# StreamDeck_CPU2-V0.net
KiCad netlist of a schematic drawn in Altium Designer
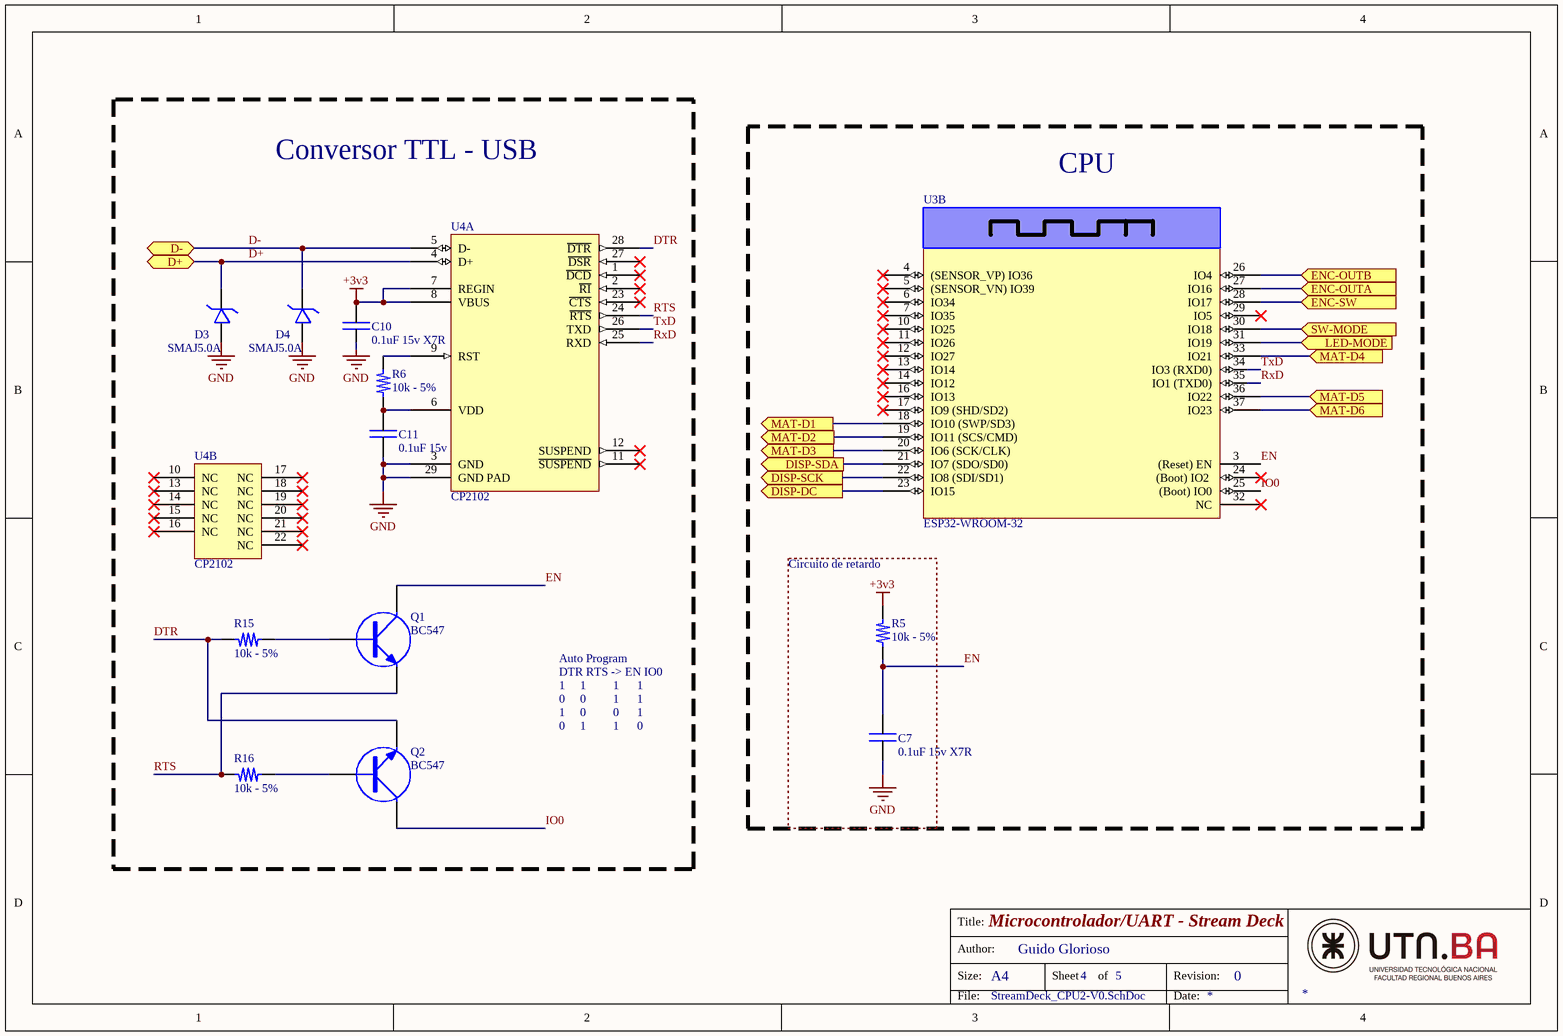
[diagram p0: StreamDeck_CPU2-V0.SchDoc]

(export (version "E")
  (design (tool "Eeschema 10.0.6"))
  (components
    (comp (ref "C7")
      (value "0.1uF 15v X7R")
      (footprint "C_0805")
      (description "Capacitor no polarizado")
      (libsource (lib "StreamDeck-V0") (part "Capacitor NP"))
    )
    (comp (ref "C10")
      (value "0.1uF 15v X7R")
      (footprint "C_0805")
      (description "Capacitor no polarizado")
      (libsource (lib "StreamDeck-V0") (part "Capacitor NP"))
    )
    (comp (ref "C11")
      (value "0.1uF 15v X7R")
      (footprint "C_0805")
      (description "Capacitor no polarizado")
      (libsource (lib "StreamDeck-V0") (part "Capacitor NP"))
    )
    (comp (ref "D3")
      (value "SMAJ5.0A")
      (footprint "D_SMA")
      (description "Diodo TVS")
      (libsource (lib "StreamDeck-V0") (part "Diodo TVS"))
    )
    (comp (ref "D4")
      (value "SMAJ5.0A")
      (footprint "D_SMA")
      (description "Diodo TVS")
      (libsource (lib "StreamDeck-V0") (part "Diodo TVS"))
    )
    (comp (ref "Q1")
      (value "BC547")
      (footprint "SOT_23")
      (description "Transistor bipolar NPN - Encapsulado SOT-23")
      (libsource (lib "StreamDeck-V0") (part "Transistor NPN"))
    )
    (comp (ref "Q2")
      (value "BC547")
      (footprint "SOT_23")
      (description "Transistor bipolar NPN - Encapsulado SOT-23")
      (libsource (lib "StreamDeck-V0") (part "Transistor NPN"))
    )
    (comp (ref "R5")
      (value "10k - 5%")
      (footprint "R_0805")
      (description "Resistor")
      (libsource (lib "StreamDeck-V0") (part "Resistor"))
    )
    (comp (ref "R6")
      (value "10k - 5%")
      (footprint "R_0805")
      (description "Resistor")
      (libsource (lib "StreamDeck-V0") (part "Resistor"))
    )
    (comp (ref "R15")
      (value "10k - 5%")
      (footprint "R_0805")
      (description "Resistor")
      (libsource (lib "StreamDeck-V0") (part "Resistor"))
    )
    (comp (ref "R16")
      (value "10k - 5%")
      (footprint "R_0805")
      (description "Resistor")
      (libsource (lib "StreamDeck-V0") (part "Resistor"))
    )
    (comp (ref "U3")
      (value "ESP32-WROOM-32")
      (footprint "Espressif ESP32-WROOM-32")
      (libsource (lib "StreamDeck-V0") (part "ESP32"))
    )
    (comp (ref "U4")
      (value "CP2102")
      (footprint "QFN-28N")
      (description "SINGLE-CHIP USB TO UART BRIDGE WITH BUILT IN 3V3 REGULATOR")
      (libsource (lib "StreamDeck-V0") (part "CP2102"))
    )
  )
  (nets
    (net (code "1") (name "+3v3") (class "Default")
      (node (ref "C10") (pin "1") (pinfunction "1_1") (pintype "passive"))
      (node (ref "R5") (pin "2") (pinfunction "2_2") (pintype "passive"))
      (node (ref "U4") (pin "7") (pinfunction "REGIN_7") (pintype "passive"))
      (node (ref "U4") (pin "8") (pinfunction "VBUS_8") (pintype "power_in"))
    )
    (net (code "2") (name "/D+") (class "Default")
      (node (ref "D3") (pin "2") (pinfunction "catodo_2") (pintype "passive"))
      (node (ref "U4") (pin "4") (pinfunction "D+_4") (pintype "bidirectional"))
    )
    (net (code "3") (name "/D-") (class "Default")
      (node (ref "D4") (pin "2") (pinfunction "catodo_2") (pintype "passive"))
      (node (ref "U4") (pin "5") (pinfunction "D-_5") (pintype "bidirectional"))
    )
    (net (code "4") (name "/DISP-DC") (class "Default")
      (node (ref "U3") (pin "23") (pinfunction "IO15_23") (pintype "bidirectional"))
    )
    (net (code "5") (name "/DISP-SCK") (class "Default")
      (node (ref "U3") (pin "22") (pinfunction "IO8_(SDI/SD1)_22") (pintype "bidirectional"))
    )
    (net (code "6") (name "/DISP-SDA") (class "Default")
      (node (ref "U3") (pin "21") (pinfunction "IO7_(SDO/SD0)_21") (pintype "bidirectional"))
    )
    (net (code "7") (name "/DTR") (class "Default")
      (node (ref "Q2") (pin "3") (pinfunction "E_3") (pintype "passive"))
      (node (ref "R15") (pin "2") (pinfunction "2_2") (pintype "passive"))
      (node (ref "U4") (pin "28") (pinfunction "~{DTR}_28") (pintype "output"))
    )
    (net (code "8") (name "/EN") (class "Default")
      (node (ref "C7") (pin "1") (pinfunction "1_1") (pintype "passive"))
      (node (ref "Q1") (pin "2") (pinfunction "C_2") (pintype "passive"))
      (node (ref "R5") (pin "1") (pinfunction "1_1") (pintype "passive"))
      (node (ref "U3") (pin "3") (pinfunction "(Reset)_EN_3") (pintype "passive"))
    )
    (net (code "9") (name "/ENC-OUTA") (class "Default")
      (node (ref "U3") (pin "27") (pinfunction "IO16_27") (pintype "bidirectional"))
    )
    (net (code "10") (name "/ENC-OUTB") (class "Default")
      (node (ref "U3") (pin "26") (pinfunction "IO4_26") (pintype "bidirectional"))
    )
    (net (code "11") (name "/ENC-SW") (class "Default")
      (node (ref "U3") (pin "28") (pinfunction "IO17_28") (pintype "bidirectional"))
    )
    (net (code "12") (name "/IO0") (class "Default")
      (node (ref "Q2") (pin "2") (pinfunction "C_2") (pintype "passive"))
      (node (ref "U3") (pin "25") (pinfunction "(Boot)_IO0_25") (pintype "bidirectional"))
    )
    (net (code "13") (name "/LED-MODE") (class "Default")
      (node (ref "U3") (pin "31") (pinfunction "IO19_31") (pintype "bidirectional"))
    )
    (net (code "14") (name "/MAT-D1") (class "Default")
      (node (ref "U3") (pin "18") (pinfunction "IO10_(SWP/SD3)_18") (pintype "bidirectional"))
    )
    (net (code "15") (name "/MAT-D2") (class "Default")
      (node (ref "U3") (pin "19") (pinfunction "IO11_(SCS/CMD)_19") (pintype "bidirectional"))
    )
    (net (code "16") (name "/MAT-D3") (class "Default")
      (node (ref "U3") (pin "20") (pinfunction "IO6_(SCK/CLK)_20") (pintype "bidirectional"))
    )
    (net (code "17") (name "/MAT-D4") (class "Default")
      (node (ref "U3") (pin "33") (pinfunction "IO21_33") (pintype "bidirectional"))
    )
    (net (code "18") (name "/MAT-D5") (class "Default")
      (node (ref "U3") (pin "36") (pinfunction "IO22_36") (pintype "bidirectional"))
    )
    (net (code "19") (name "/MAT-D6") (class "Default")
      (node (ref "U3") (pin "37") (pinfunction "IO23_37") (pintype "bidirectional"))
    )
    (net (code "20") (name "/RTS") (class "Default")
      (node (ref "Q1") (pin "3") (pinfunction "E_3") (pintype "passive"))
      (node (ref "R16") (pin "2") (pinfunction "2_2") (pintype "passive"))
      (node (ref "U4") (pin "24") (pinfunction "~{RTS}_24") (pintype "output"))
    )
    (net (code "21") (name "/RxD") (class "Default")
      (node (ref "U3") (pin "35") (pinfunction "IO1_(TXD0)_35") (pintype "bidirectional"))
      (node (ref "U4") (pin "25") (pinfunction "RXD_25") (pintype "input"))
    )
    (net (code "22") (name "/SW-MODE") (class "Default")
      (node (ref "U3") (pin "30") (pinfunction "IO18_30") (pintype "bidirectional"))
    )
    (net (code "23") (name "/TxD") (class "Default")
      (node (ref "U3") (pin "34") (pinfunction "IO3_(RXD0)_34") (pintype "bidirectional"))
      (node (ref "U4") (pin "26") (pinfunction "TXD_26") (pintype "output"))
    )
    (net (code "24") (name "GND") (class "Default")
      (node (ref "C10") (pin "2") (pinfunction "2_2") (pintype "passive"))
      (node (ref "C11") (pin "2") (pinfunction "2_2") (pintype "passive"))
      (node (ref "C7") (pin "2") (pinfunction "2_2") (pintype "passive"))
      (node (ref "D3") (pin "1") (pinfunction "anodo_1") (pintype "passive"))
      (node (ref "D4") (pin "1") (pinfunction "anodo_1") (pintype "passive"))
      (node (ref "U4") (pin "29") (pinfunction "GND_PAD_29") (pintype "passive"))
      (node (ref "U4") (pin "3") (pinfunction "GND_3") (pintype "passive"))
    )
    (net (code "25") (name "Net-(Q1-B)") (class "Default")
      (node (ref "Q1") (pin "1") (pinfunction "B_1") (pintype "passive"))
      (node (ref "R15") (pin "1") (pinfunction "1_1") (pintype "passive"))
    )
    (net (code "26") (name "Net-(Q2-B)") (class "Default")
      (node (ref "Q2") (pin "1") (pinfunction "B_1") (pintype "passive"))
      (node (ref "R16") (pin "1") (pinfunction "1_1") (pintype "passive"))
    )
    (net (code "27") (name "Net-(U4A-RST)") (class "Default")
      (node (ref "R6") (pin "2") (pinfunction "2_2") (pintype "passive"))
      (node (ref "U4") (pin "9") (pinfunction "RST_9") (pintype "input"))
    )
    (net (code "28") (name "Net-(U4A-VDD)") (class "Default")
      (node (ref "C11") (pin "1") (pinfunction "1_1") (pintype "passive"))
      (node (ref "R6") (pin "1") (pinfunction "1_1") (pintype "passive"))
      (node (ref "U4") (pin "6") (pinfunction "VDD_6") (pintype "power_in"))
    )
    (net (code "29") (name "unconnected-(U3B-(Boot)_IO2-Pad24)") (class "Default")
      (node (ref "U3") (pin "24") (pinfunction "(Boot)_IO2_24") (pintype "bidirectional+no_connect"))
    )
    (net (code "30") (name "unconnected-(U3B-(SENSOR_VN)_IO39-Pad5)") (class "Default")
      (node (ref "U3") (pin "5") (pinfunction "(SENSOR_VN)_IO39_5") (pintype "bidirectional+no_connect"))
    )
    (net (code "31") (name "unconnected-(U3B-(SENSOR_VP)_IO36-Pad4)") (class "Default")
      (node (ref "U3") (pin "4") (pinfunction "(SENSOR_VP)_IO36_4") (pintype "bidirectional+no_connect"))
    )
    (net (code "32") (name "unconnected-(U3B-IO5-Pad29)") (class "Default")
      (node (ref "U3") (pin "29") (pinfunction "IO5_29") (pintype "bidirectional+no_connect"))
    )
    (net (code "33") (name "unconnected-(U3B-IO9_(SHD{slash}SD2)-Pad17)") (class "Default")
      (node (ref "U3") (pin "17") (pinfunction "IO9_(SHD/SD2)_17") (pintype "bidirectional+no_connect"))
    )
    (net (code "34") (name "unconnected-(U3B-IO12-Pad14)") (class "Default")
      (node (ref "U3") (pin "14") (pinfunction "IO12_14") (pintype "bidirectional+no_connect"))
    )
    (net (code "35") (name "unconnected-(U3B-IO13-Pad16)") (class "Default")
      (node (ref "U3") (pin "16") (pinfunction "IO13_16") (pintype "bidirectional+no_connect"))
    )
    (net (code "36") (name "unconnected-(U3B-IO14-Pad13)") (class "Default")
      (node (ref "U3") (pin "13") (pinfunction "IO14_13") (pintype "bidirectional+no_connect"))
    )
    (net (code "37") (name "unconnected-(U3B-IO25-Pad10)") (class "Default")
      (node (ref "U3") (pin "10") (pinfunction "IO25_10") (pintype "bidirectional+no_connect"))
    )
    (net (code "38") (name "unconnected-(U3B-IO26-Pad11)") (class "Default")
      (node (ref "U3") (pin "11") (pinfunction "IO26_11") (pintype "bidirectional+no_connect"))
    )
    (net (code "39") (name "unconnected-(U3B-IO27-Pad12)") (class "Default")
      (node (ref "U3") (pin "12") (pinfunction "IO27_12") (pintype "bidirectional+no_connect"))
    )
    (net (code "40") (name "unconnected-(U3B-IO34-Pad6)") (class "Default")
      (node (ref "U3") (pin "6") (pinfunction "IO34_6") (pintype "bidirectional+no_connect"))
    )
    (net (code "41") (name "unconnected-(U3B-IO35-Pad7)") (class "Default")
      (node (ref "U3") (pin "7") (pinfunction "IO35_7") (pintype "bidirectional+no_connect"))
    )
    (net (code "42") (name "unconnected-(U3B-NC-Pad32)") (class "Default")
      (node (ref "U3") (pin "32") (pinfunction "NC_32") (pintype "passive+no_connect"))
    )
    (net (code "43") (name "unconnected-(U4A-SUSPEND-Pad12)") (class "Default")
      (node (ref "U4") (pin "12") (pinfunction "SUSPEND_12") (pintype "output+no_connect"))
    )
    (net (code "44") (name "unconnected-(U4A-~{CTS}-Pad23)") (class "Default")
      (node (ref "U4") (pin "23") (pinfunction "~{CTS}_23") (pintype "input+no_connect"))
    )
    (net (code "45") (name "unconnected-(U4A-~{DCD}-Pad1)") (class "Default")
      (node (ref "U4") (pin "1") (pinfunction "~{DCD}_1") (pintype "input+no_connect"))
    )
    (net (code "46") (name "unconnected-(U4A-~{DSR}-Pad27)") (class "Default")
      (node (ref "U4") (pin "27") (pinfunction "~{DSR}_27") (pintype "input+no_connect"))
    )
    (net (code "47") (name "unconnected-(U4A-~{RI}-Pad2)") (class "Default")
      (node (ref "U4") (pin "2") (pinfunction "~{RI}_2") (pintype "input+no_connect"))
    )
    (net (code "48") (name "unconnected-(U4A-~{SUSPEND}-Pad11)") (class "Default")
      (node (ref "U4") (pin "11") (pinfunction "~{SUSPEND}_11") (pintype "output+no_connect"))
    )
    (net (code "49") (name "unconnected-(U4B-NC-Pad10)") (class "Default")
      (node (ref "U4") (pin "10") (pinfunction "NC_10") (pintype "passive+no_connect"))
    )
    (net (code "50") (name "unconnected-(U4B-NC-Pad13)") (class "Default")
      (node (ref "U4") (pin "13") (pinfunction "NC_13") (pintype "passive+no_connect"))
    )
    (net (code "51") (name "unconnected-(U4B-NC-Pad14)") (class "Default")
      (node (ref "U4") (pin "14") (pinfunction "NC_14") (pintype "passive+no_connect"))
    )
    (net (code "52") (name "unconnected-(U4B-NC-Pad15)") (class "Default")
      (node (ref "U4") (pin "15") (pinfunction "NC_15") (pintype "passive+no_connect"))
    )
    (net (code "53") (name "unconnected-(U4B-NC-Pad16)") (class "Default")
      (node (ref "U4") (pin "16") (pinfunction "NC_16") (pintype "passive+no_connect"))
    )
    (net (code "54") (name "unconnected-(U4B-NC-Pad17)") (class "Default")
      (node (ref "U4") (pin "17") (pinfunction "NC_17") (pintype "passive+no_connect"))
    )
    (net (code "55") (name "unconnected-(U4B-NC-Pad18)") (class "Default")
      (node (ref "U4") (pin "18") (pinfunction "NC_18") (pintype "passive+no_connect"))
    )
    (net (code "56") (name "unconnected-(U4B-NC-Pad19)") (class "Default")
      (node (ref "U4") (pin "19") (pinfunction "NC_19") (pintype "passive+no_connect"))
    )
    (net (code "57") (name "unconnected-(U4B-NC-Pad20)") (class "Default")
      (node (ref "U4") (pin "20") (pinfunction "NC_20") (pintype "passive+no_connect"))
    )
    (net (code "58") (name "unconnected-(U4B-NC-Pad21)") (class "Default")
      (node (ref "U4") (pin "21") (pinfunction "NC_21") (pintype "passive+no_connect"))
    )
    (net (code "59") (name "unconnected-(U4B-NC-Pad22)") (class "Default")
      (node (ref "U4") (pin "22") (pinfunction "NC_22") (pintype "passive+no_connect"))
    )
  )
)
